# Isolators.net
KiCad netlist of a schematic drawn in Altium Designer
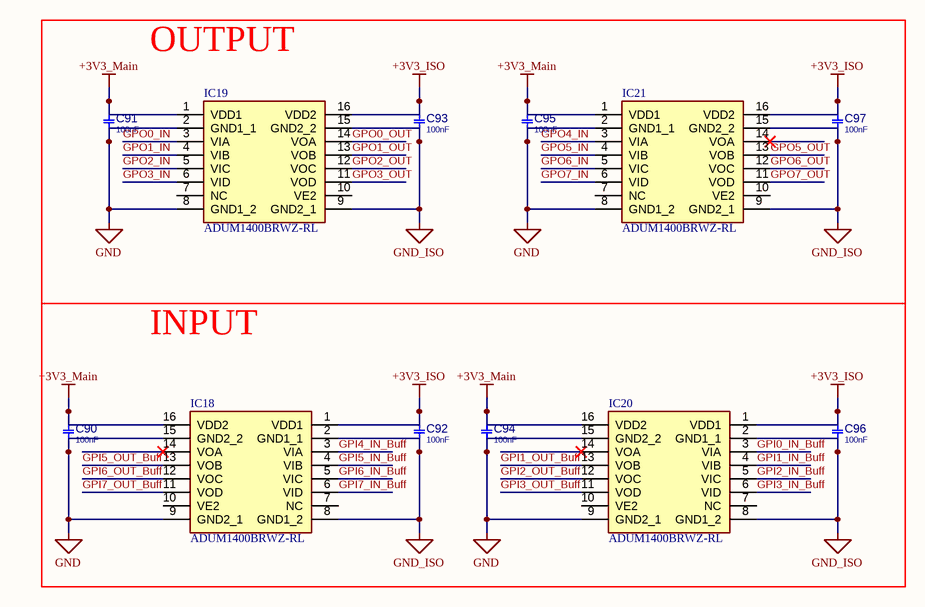
[diagram p0: Isolators.SchDoc]

(export (version "E")
  (design (tool "Eeschema 10.0.6"))
  (components
    (comp (ref "C90")
      (value "100nF")
      (footprint "C0603")
      (description "CAP, MLCC")
      (fields (field (name "MANF_P#") "C1005X7R1H104K050BB") (field (name "MANF") "TDK"))
      (libsource (lib "mlcc_smd_passive") (part "CAP_SMD_MLCC_2.2u50V_0603"))
    )
    (comp (ref "C91")
      (value "100nF")
      (footprint "C0603")
      (description "CAP, MLCC")
      (fields (field (name "MANF_P#") "C1005X7R1H104K050BB") (field (name "MANF") "TDK"))
      (libsource (lib "mlcc_smd_passive") (part "CAP_SMD_MLCC_2.2u50V_0603"))
    )
    (comp (ref "C92")
      (value "100nF")
      (footprint "C0603")
      (description "CAP, MLCC")
      (fields (field (name "MANF_P#") "C1005X7R1H104K050BB") (field (name "MANF") "TDK"))
      (libsource (lib "mlcc_smd_passive") (part "CAP_SMD_MLCC_2.2u50V_0603"))
    )
    (comp (ref "C93")
      (value "100nF")
      (footprint "C0603")
      (description "CAP, MLCC")
      (fields (field (name "MANF_P#") "C1005X7R1H104K050BB") (field (name "MANF") "TDK"))
      (libsource (lib "mlcc_smd_passive") (part "CAP_SMD_MLCC_2.2u50V_0603"))
    )
    (comp (ref "C94")
      (value "100nF")
      (footprint "C0603")
      (description "CAP, MLCC")
      (fields (field (name "MANF_P#") "C1005X7R1H104K050BB") (field (name "MANF") "TDK"))
      (libsource (lib "mlcc_smd_passive") (part "CAP_SMD_MLCC_2.2u50V_0603"))
    )
    (comp (ref "C95")
      (value "100nF")
      (footprint "C0603")
      (description "CAP, MLCC")
      (fields (field (name "MANF_P#") "C1005X7R1H104K050BB") (field (name "MANF") "TDK"))
      (libsource (lib "mlcc_smd_passive") (part "CAP_SMD_MLCC_2.2u50V_0603"))
    )
    (comp (ref "C96")
      (value "100nF")
      (footprint "C0603")
      (description "CAP, MLCC")
      (fields (field (name "MANF_P#") "C1005X7R1H104K050BB") (field (name "MANF") "TDK"))
      (libsource (lib "mlcc_smd_passive") (part "CAP_SMD_MLCC_2.2u50V_0603"))
    )
    (comp (ref "C97")
      (value "100nF")
      (footprint "C0603")
      (description "CAP, MLCC")
      (fields (field (name "MANF_P#") "C1005X7R1H104K050BB") (field (name "MANF") "TDK"))
      (libsource (lib "mlcc_smd_passive") (part "CAP_SMD_MLCC_2.2u50V_0603"))
    )
    (comp (ref "IC18")
      (value "ADUM1400BRWZ-RL")
      (footprint "SamacSys:SOIC127P1032X265-16N")
      (description "Integrated Circuit")
      (fields (field (name "MOUSER PART NUMBER") "584-ADUM1400BRWZ-R"))
      (libsource (lib "") (part "ADUM1400BRWZ-RL_1"))
    )
    (comp (ref "IC19")
      (value "ADUM1400BRWZ-RL")
      (footprint "SamacSys:SOIC127P1032X265-16N")
      (description "Integrated Circuit")
      (fields (field (name "MOUSER PART NUMBER") "584-ADUM1400BRWZ-R"))
      (libsource (lib "*") (part "ADUM1400BRWZ-RL"))
    )
    (comp (ref "IC20")
      (value "ADUM1400BRWZ-RL")
      (footprint "SamacSys:SOIC127P1032X265-16N")
      (description "Integrated Circuit")
      (fields (field (name "MOUSER PART NUMBER") "584-ADUM1400BRWZ-R"))
      (libsource (lib "") (part "ADUM1400BRWZ-RL_1"))
    )
    (comp (ref "IC21")
      (value "ADUM1400BRWZ-RL")
      (footprint "SamacSys:SOIC127P1032X265-16N")
      (description "Integrated Circuit")
      (fields (field (name "MOUSER PART NUMBER") "584-ADUM1400BRWZ-R"))
      (libsource (lib "*") (part "ADUM1400BRWZ-RL"))
    )
  )
  (nets
    (net (code "1") (name "+3V3_ISO") (class "Default")
      (node (ref "C92") (pin "1") (pinfunction "1_1") (pintype "passive"))
      (node (ref "C93") (pin "1") (pinfunction "1_1") (pintype "passive"))
      (node (ref "C96") (pin "1") (pinfunction "1_1") (pintype "passive"))
      (node (ref "C97") (pin "1") (pinfunction "1_1") (pintype "passive"))
      (node (ref "IC18") (pin "1") (pinfunction "VDD1_1") (pintype "passive"))
      (node (ref "IC19") (pin "16") (pinfunction "VDD2_16") (pintype "passive"))
      (node (ref "IC20") (pin "1") (pinfunction "VDD1_1") (pintype "passive"))
      (node (ref "IC21") (pin "16") (pinfunction "VDD2_16") (pintype "passive"))
    )
    (net (code "2") (name "+3V3_Main") (class "Default")
      (node (ref "C90") (pin "1") (pinfunction "1_1") (pintype "passive"))
      (node (ref "C91") (pin "1") (pinfunction "1_1") (pintype "passive"))
      (node (ref "C94") (pin "1") (pinfunction "1_1") (pintype "passive"))
      (node (ref "C95") (pin "1") (pinfunction "1_1") (pintype "passive"))
      (node (ref "IC18") (pin "16") (pinfunction "VDD2_16") (pintype "passive"))
      (node (ref "IC19") (pin "1") (pinfunction "VDD1_1") (pintype "passive"))
      (node (ref "IC20") (pin "16") (pinfunction "VDD2_16") (pintype "passive"))
      (node (ref "IC21") (pin "1") (pinfunction "VDD1_1") (pintype "passive"))
    )
    (net (code "3") (name "/GPI0_IN_Buff") (class "Default")
      (node (ref "IC20") (pin "3") (pinfunction "VIA_3") (pintype "passive"))
    )
    (net (code "4") (name "/GPI1_IN_Buff") (class "Default")
      (node (ref "IC20") (pin "4") (pinfunction "VIB_4") (pintype "passive"))
    )
    (net (code "5") (name "/GPI1_OUT_Buff") (class "Default")
      (node (ref "IC20") (pin "13") (pinfunction "VOB_13") (pintype "passive"))
    )
    (net (code "6") (name "/GPI2_IN_Buff") (class "Default")
      (node (ref "IC20") (pin "5") (pinfunction "VIC_5") (pintype "passive"))
    )
    (net (code "7") (name "/GPI2_OUT_Buff") (class "Default")
      (node (ref "IC20") (pin "12") (pinfunction "VOC_12") (pintype "passive"))
    )
    (net (code "8") (name "/GPI3_IN_Buff") (class "Default")
      (node (ref "IC20") (pin "6") (pinfunction "VID_6") (pintype "passive"))
    )
    (net (code "9") (name "/GPI3_OUT_Buff") (class "Default")
      (node (ref "IC20") (pin "11") (pinfunction "VOD_11") (pintype "passive"))
    )
    (net (code "10") (name "/GPI4_IN_Buff") (class "Default")
      (node (ref "IC18") (pin "3") (pinfunction "VIA_3") (pintype "passive"))
    )
    (net (code "11") (name "/GPI5_IN_Buff") (class "Default")
      (node (ref "IC18") (pin "4") (pinfunction "VIB_4") (pintype "passive"))
    )
    (net (code "12") (name "/GPI5_OUT_Buff") (class "Default")
      (node (ref "IC18") (pin "13") (pinfunction "VOB_13") (pintype "passive"))
    )
    (net (code "13") (name "/GPI6_IN_Buff") (class "Default")
      (node (ref "IC18") (pin "5") (pinfunction "VIC_5") (pintype "passive"))
    )
    (net (code "14") (name "/GPI6_OUT_Buff") (class "Default")
      (node (ref "IC18") (pin "12") (pinfunction "VOC_12") (pintype "passive"))
    )
    (net (code "15") (name "/GPI7_IN_Buff") (class "Default")
      (node (ref "IC18") (pin "6") (pinfunction "VID_6") (pintype "passive"))
    )
    (net (code "16") (name "/GPI7_OUT_Buff") (class "Default")
      (node (ref "IC18") (pin "11") (pinfunction "VOD_11") (pintype "passive"))
    )
    (net (code "17") (name "/GPO0_IN") (class "Default")
      (node (ref "IC19") (pin "3") (pinfunction "VIA_3") (pintype "passive"))
    )
    (net (code "18") (name "/GPO0_OUT") (class "Default")
      (node (ref "IC19") (pin "14") (pinfunction "VOA_14") (pintype "passive"))
    )
    (net (code "19") (name "/GPO1_IN") (class "Default")
      (node (ref "IC19") (pin "4") (pinfunction "VIB_4") (pintype "passive"))
    )
    (net (code "20") (name "/GPO1_OUT") (class "Default")
      (node (ref "IC19") (pin "13") (pinfunction "VOB_13") (pintype "passive"))
    )
    (net (code "21") (name "/GPO2_IN") (class "Default")
      (node (ref "IC19") (pin "5") (pinfunction "VIC_5") (pintype "passive"))
    )
    (net (code "22") (name "/GPO2_OUT") (class "Default")
      (node (ref "IC19") (pin "12") (pinfunction "VOC_12") (pintype "passive"))
    )
    (net (code "23") (name "/GPO3_IN") (class "Default")
      (node (ref "IC19") (pin "6") (pinfunction "VID_6") (pintype "passive"))
    )
    (net (code "24") (name "/GPO3_OUT") (class "Default")
      (node (ref "IC19") (pin "11") (pinfunction "VOD_11") (pintype "passive"))
    )
    (net (code "25") (name "/GPO4_IN") (class "Default")
      (node (ref "IC21") (pin "3") (pinfunction "VIA_3") (pintype "passive"))
    )
    (net (code "26") (name "/GPO5_IN") (class "Default")
      (node (ref "IC21") (pin "4") (pinfunction "VIB_4") (pintype "passive"))
    )
    (net (code "27") (name "/GPO5_OUT") (class "Default")
      (node (ref "IC21") (pin "13") (pinfunction "VOB_13") (pintype "passive"))
    )
    (net (code "28") (name "/GPO6_IN") (class "Default")
      (node (ref "IC21") (pin "5") (pinfunction "VIC_5") (pintype "passive"))
    )
    (net (code "29") (name "/GPO6_OUT") (class "Default")
      (node (ref "IC21") (pin "12") (pinfunction "VOC_12") (pintype "passive"))
    )
    (net (code "30") (name "/GPO7_IN") (class "Default")
      (node (ref "IC21") (pin "6") (pinfunction "VID_6") (pintype "passive"))
    )
    (net (code "31") (name "/GPO7_OUT") (class "Default")
      (node (ref "IC21") (pin "11") (pinfunction "VOD_11") (pintype "passive"))
    )
    (net (code "32") (name "GND") (class "Default")
      (node (ref "C90") (pin "2") (pinfunction "2_2") (pintype "passive"))
      (node (ref "C91") (pin "2") (pinfunction "2_2") (pintype "passive"))
      (node (ref "C94") (pin "2") (pinfunction "2_2") (pintype "passive"))
      (node (ref "C95") (pin "2") (pinfunction "2_2") (pintype "passive"))
      (node (ref "IC18") (pin "15") (pinfunction "GND2_2_15") (pintype "passive"))
      (node (ref "IC18") (pin "9") (pinfunction "GND2_1_9") (pintype "passive"))
      (node (ref "IC19") (pin "2") (pinfunction "GND1_1_2") (pintype "passive"))
      (node (ref "IC19") (pin "8") (pinfunction "GND1_2_8") (pintype "passive"))
      (node (ref "IC20") (pin "15") (pinfunction "GND2_2_15") (pintype "passive"))
      (node (ref "IC20") (pin "9") (pinfunction "GND2_1_9") (pintype "passive"))
      (node (ref "IC21") (pin "2") (pinfunction "GND1_1_2") (pintype "passive"))
      (node (ref "IC21") (pin "8") (pinfunction "GND1_2_8") (pintype "passive"))
    )
    (net (code "33") (name "GND_ISO") (class "Default")
      (node (ref "C92") (pin "2") (pinfunction "2_2") (pintype "passive"))
      (node (ref "C93") (pin "2") (pinfunction "2_2") (pintype "passive"))
      (node (ref "C96") (pin "2") (pinfunction "2_2") (pintype "passive"))
      (node (ref "C97") (pin "2") (pinfunction "2_2") (pintype "passive"))
      (node (ref "IC18") (pin "2") (pinfunction "GND1_1_2") (pintype "passive"))
      (node (ref "IC18") (pin "8") (pinfunction "GND1_2_8") (pintype "passive"))
      (node (ref "IC19") (pin "15") (pinfunction "GND2_2_15") (pintype "passive"))
      (node (ref "IC19") (pin "9") (pinfunction "GND2_1_9") (pintype "passive"))
      (node (ref "IC20") (pin "2") (pinfunction "GND1_1_2") (pintype "passive"))
      (node (ref "IC20") (pin "8") (pinfunction "GND1_2_8") (pintype "passive"))
      (node (ref "IC21") (pin "15") (pinfunction "GND2_2_15") (pintype "passive"))
      (node (ref "IC21") (pin "9") (pinfunction "GND2_1_9") (pintype "passive"))
    )
    (net (code "34") (name "unconnected-(IC18-NC-Pad7)") (class "Default")
      (node (ref "IC18") (pin "7") (pinfunction "NC_7") (pintype "passive"))
    )
    (net (code "35") (name "unconnected-(IC18-VE2-Pad10)") (class "Default")
      (node (ref "IC18") (pin "10") (pinfunction "VE2_10") (pintype "passive"))
    )
    (net (code "36") (name "unconnected-(IC18-VOA-Pad14)") (class "Default")
      (node (ref "IC18") (pin "14") (pinfunction "VOA_14") (pintype "passive+no_connect"))
    )
    (net (code "37") (name "unconnected-(IC19-NC-Pad7)") (class "Default")
      (node (ref "IC19") (pin "7") (pinfunction "NC_7") (pintype "passive"))
    )
    (net (code "38") (name "unconnected-(IC19-VE2-Pad10)") (class "Default")
      (node (ref "IC19") (pin "10") (pinfunction "VE2_10") (pintype "passive"))
    )
    (net (code "39") (name "unconnected-(IC20-NC-Pad7)") (class "Default")
      (node (ref "IC20") (pin "7") (pinfunction "NC_7") (pintype "passive"))
    )
    (net (code "40") (name "unconnected-(IC20-VE2-Pad10)") (class "Default")
      (node (ref "IC20") (pin "10") (pinfunction "VE2_10") (pintype "passive"))
    )
    (net (code "41") (name "unconnected-(IC20-VOA-Pad14)") (class "Default")
      (node (ref "IC20") (pin "14") (pinfunction "VOA_14") (pintype "passive+no_connect"))
    )
    (net (code "42") (name "unconnected-(IC21-NC-Pad7)") (class "Default")
      (node (ref "IC21") (pin "7") (pinfunction "NC_7") (pintype "passive"))
    )
    (net (code "43") (name "unconnected-(IC21-VE2-Pad10)") (class "Default")
      (node (ref "IC21") (pin "10") (pinfunction "VE2_10") (pintype "passive"))
    )
    (net (code "44") (name "unconnected-(IC21-VOA-Pad14)") (class "Default")
      (node (ref "IC21") (pin "14") (pinfunction "VOA_14") (pintype "passive+no_connect"))
    )
  )
)
